# FAN-zero25-SHIM.net
KiCad netlist of a schematic drawn in EAGLE
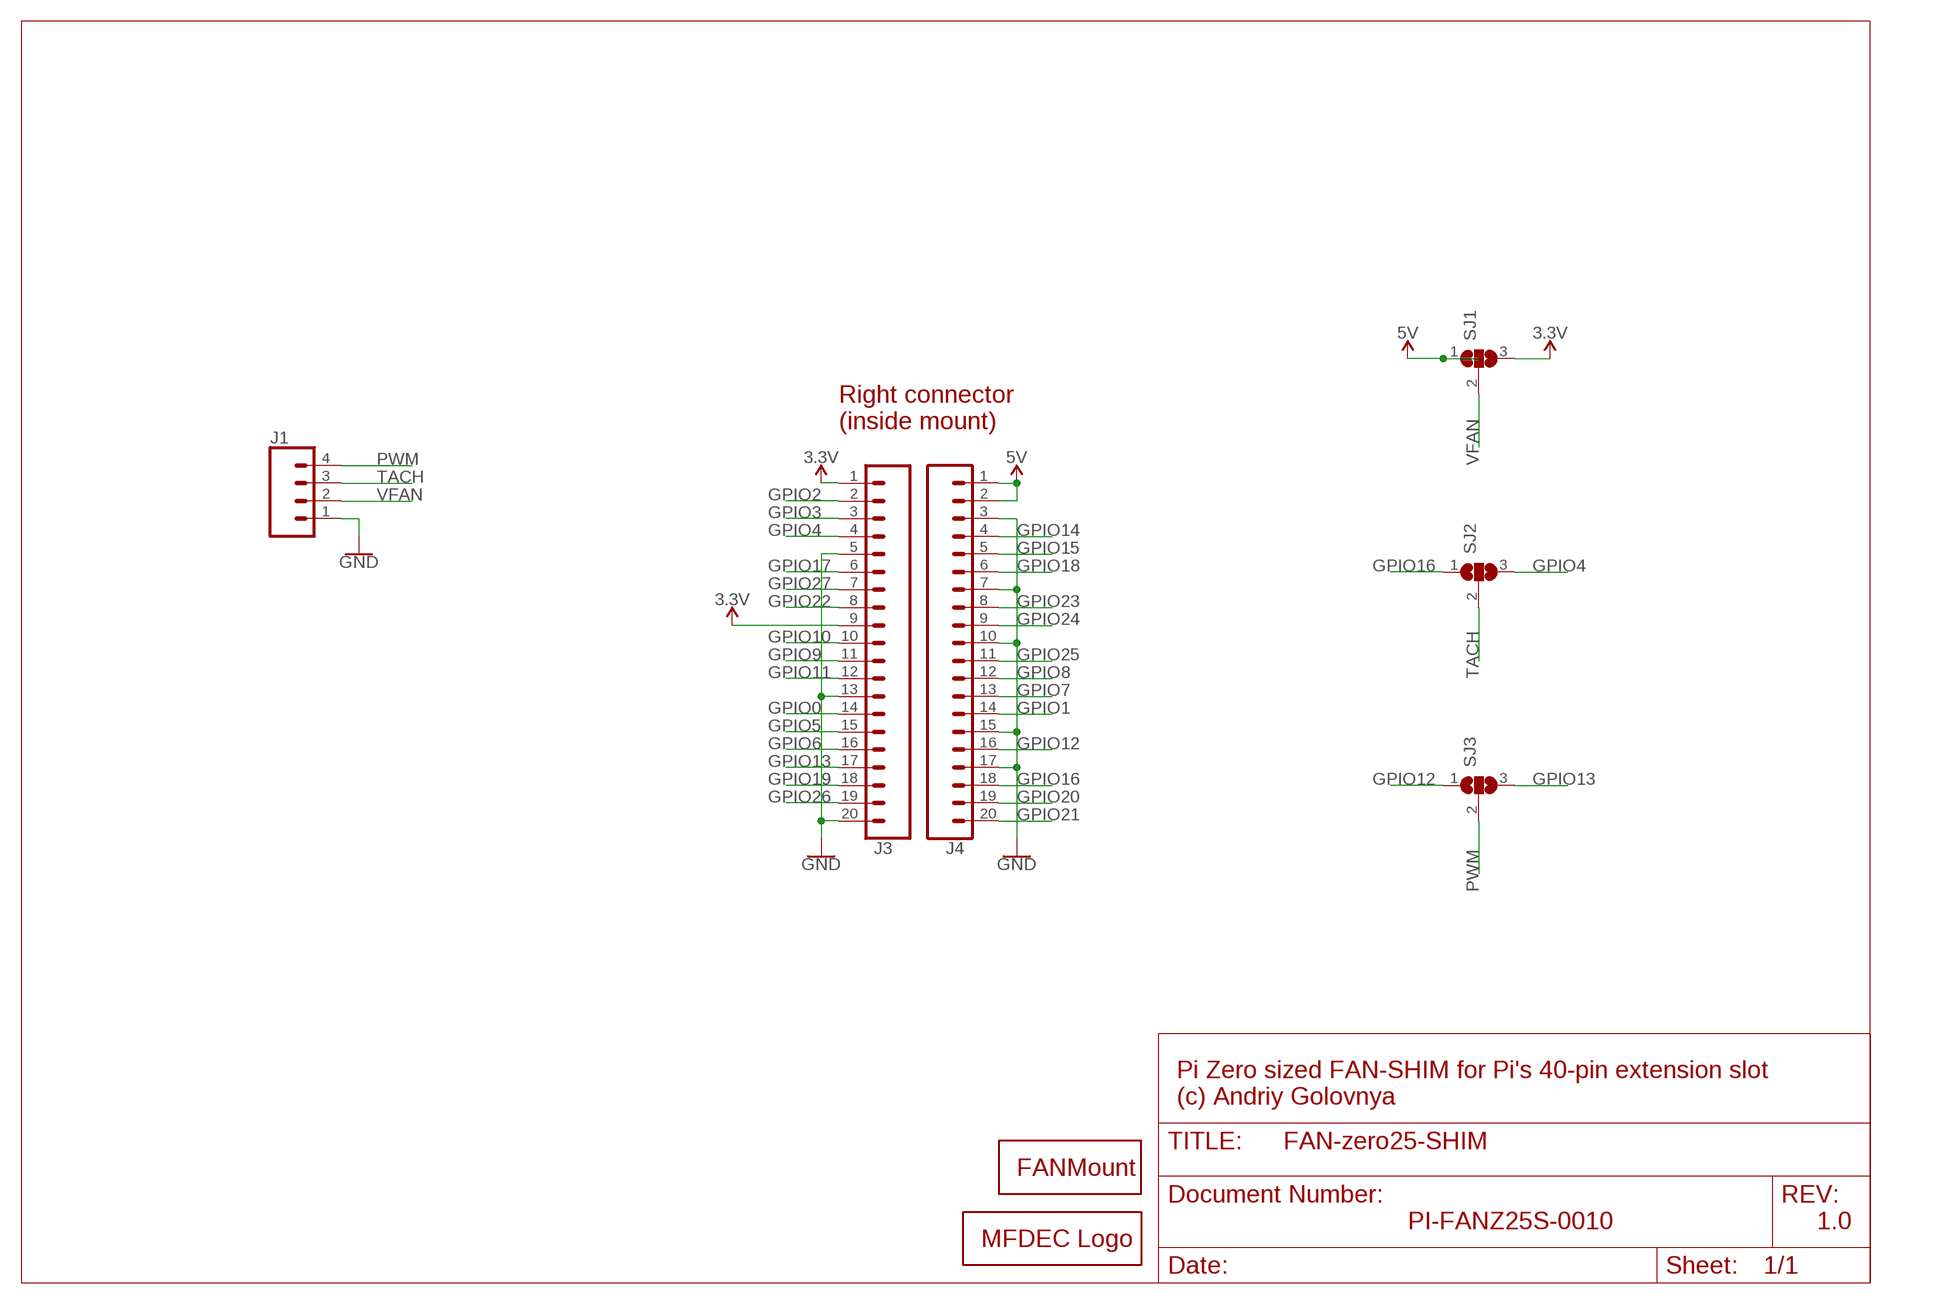
[diagram p0: schematic, sheet 1]

(export (version "E")
  (design (tool "Eeschema 10.0.6"))
  (components
    (comp (ref "FAN1")
      (value "FAN25HO")
      (footprint "eagle-import:FAN25HO")
      (libsource (lib "eagle-import") (part "FAN25HO"))
    )
    (comp (ref "J1")
      (value "CONN_04")
      (footprint "eagle-import:1X04")
      (libsource (lib "eagle-import") (part "CONN_04"))
    )
    (comp (ref "J3")
      (value "CONN_20LOCK")
      (footprint "eagle-import:1X20_LOCK")
      (libsource (lib "eagle-import") (part "CONN_20LOCK"))
    )
    (comp (ref "J4")
      (value "CONN_20LOCK")
      (footprint "eagle-import:1X20_LOCK")
      (libsource (lib "eagle-import") (part "CONN_20LOCK"))
    )
    (comp (ref "LOGO1")
      (value "MFDECLOGO_L_30MM")
      (footprint "eagle-import:MFDEC_L_30MM")
      (libsource (lib "eagle-import") (part "MFDECLOGO_L_30MM"))
    )
    (comp (ref "SJ1")
      (value "SJ2")
      (footprint "eagle-import:SJ_2")
      (libsource (lib "eagle-import") (part "SJ2"))
    )
    (comp (ref "SJ2")
      (value "SJ2")
      (footprint "eagle-import:SJ_2")
      (libsource (lib "eagle-import") (part "SJ2"))
    )
    (comp (ref "SJ3")
      (value "SJ2")
      (footprint "eagle-import:SJ_2")
      (libsource (lib "eagle-import") (part "SJ2"))
    )
  )
  (nets
    (net (code "1") (name "/GPIO0") (class "Default")
      (node (ref "J3") (pin "14") (pinfunction "14_14") (pintype "passive"))
    )
    (net (code "2") (name "/GPIO1") (class "Default")
      (node (ref "J4") (pin "14") (pinfunction "14_14") (pintype "passive"))
    )
    (net (code "3") (name "/GPIO2") (class "Default")
      (node (ref "J3") (pin "2") (pinfunction "2_2") (pintype "passive"))
    )
    (net (code "4") (name "/GPIO3") (class "Default")
      (node (ref "J3") (pin "3") (pinfunction "3_3") (pintype "passive"))
    )
    (net (code "5") (name "/GPIO4") (class "Default")
      (node (ref "J3") (pin "4") (pinfunction "4_4") (pintype "passive"))
      (node (ref "SJ2") (pin "3") (pinfunction "3_3") (pintype "passive"))
    )
    (net (code "6") (name "/GPIO5") (class "Default")
      (node (ref "J3") (pin "15") (pinfunction "15_15") (pintype "passive"))
    )
    (net (code "7") (name "/GPIO6") (class "Default")
      (node (ref "J3") (pin "16") (pinfunction "16_16") (pintype "passive"))
    )
    (net (code "8") (name "/GPIO7") (class "Default")
      (node (ref "J4") (pin "13") (pinfunction "13_13") (pintype "passive"))
    )
    (net (code "9") (name "/GPIO8") (class "Default")
      (node (ref "J4") (pin "12") (pinfunction "12_12") (pintype "passive"))
    )
    (net (code "10") (name "/GPIO9") (class "Default")
      (node (ref "J3") (pin "11") (pinfunction "11_11") (pintype "passive"))
    )
    (net (code "11") (name "/GPIO10") (class "Default")
      (node (ref "J3") (pin "10") (pinfunction "10_10") (pintype "passive"))
    )
    (net (code "12") (name "/GPIO11") (class "Default")
      (node (ref "J3") (pin "12") (pinfunction "12_12") (pintype "passive"))
    )
    (net (code "13") (name "/GPIO12") (class "Default")
      (node (ref "J4") (pin "16") (pinfunction "16_16") (pintype "passive"))
      (node (ref "SJ3") (pin "1") (pinfunction "1_1") (pintype "passive"))
    )
    (net (code "14") (name "/GPIO13") (class "Default")
      (node (ref "J3") (pin "17") (pinfunction "17_17") (pintype "passive"))
      (node (ref "SJ3") (pin "3") (pinfunction "3_3") (pintype "passive"))
    )
    (net (code "15") (name "/GPIO14") (class "Default")
      (node (ref "J4") (pin "4") (pinfunction "4_4") (pintype "passive"))
    )
    (net (code "16") (name "/GPIO15") (class "Default")
      (node (ref "J4") (pin "5") (pinfunction "5_5") (pintype "passive"))
    )
    (net (code "17") (name "/GPIO16") (class "Default")
      (node (ref "J4") (pin "18") (pinfunction "18_18") (pintype "passive"))
      (node (ref "SJ2") (pin "1") (pinfunction "1_1") (pintype "passive"))
    )
    (net (code "18") (name "/GPIO17") (class "Default")
      (node (ref "J3") (pin "6") (pinfunction "6_6") (pintype "passive"))
    )
    (net (code "19") (name "/GPIO18") (class "Default")
      (node (ref "J4") (pin "6") (pinfunction "6_6") (pintype "passive"))
    )
    (net (code "20") (name "/GPIO19") (class "Default")
      (node (ref "J3") (pin "18") (pinfunction "18_18") (pintype "passive"))
    )
    (net (code "21") (name "/GPIO20") (class "Default")
      (node (ref "J4") (pin "19") (pinfunction "19_19") (pintype "passive"))
    )
    (net (code "22") (name "/GPIO21") (class "Default")
      (node (ref "J4") (pin "20") (pinfunction "20_20") (pintype "passive"))
    )
    (net (code "23") (name "/GPIO22") (class "Default")
      (node (ref "J3") (pin "8") (pinfunction "8_8") (pintype "passive"))
    )
    (net (code "24") (name "/GPIO23") (class "Default")
      (node (ref "J4") (pin "8") (pinfunction "8_8") (pintype "passive"))
    )
    (net (code "25") (name "/GPIO24") (class "Default")
      (node (ref "J4") (pin "9") (pinfunction "9_9") (pintype "passive"))
    )
    (net (code "26") (name "/GPIO25") (class "Default")
      (node (ref "J4") (pin "11") (pinfunction "11_11") (pintype "passive"))
    )
    (net (code "27") (name "/GPIO26") (class "Default")
      (node (ref "J3") (pin "19") (pinfunction "19_19") (pintype "passive"))
    )
    (net (code "28") (name "/GPIO27") (class "Default")
      (node (ref "J3") (pin "7") (pinfunction "7_7") (pintype "passive"))
    )
    (net (code "29") (name "/PWM") (class "Default")
      (node (ref "J1") (pin "4") (pinfunction "4_4") (pintype "passive"))
      (node (ref "SJ3") (pin "2") (pinfunction "2_2") (pintype "passive"))
    )
    (net (code "30") (name "/TACH") (class "Default")
      (node (ref "J1") (pin "3") (pinfunction "3_3") (pintype "passive"))
      (node (ref "SJ2") (pin "2") (pinfunction "2_2") (pintype "passive"))
    )
    (net (code "31") (name "/VFAN") (class "Default")
      (node (ref "J1") (pin "2") (pinfunction "2_2") (pintype "passive"))
      (node (ref "SJ1") (pin "2") (pinfunction "2_2") (pintype "passive"))
    )
    (net (code "32") (name "3.3V") (class "Default")
      (node (ref "J3") (pin "1") (pinfunction "1_1") (pintype "passive"))
      (node (ref "J3") (pin "9") (pinfunction "9_9") (pintype "passive"))
      (node (ref "SJ1") (pin "3") (pinfunction "3_3") (pintype "passive"))
    )
    (net (code "33") (name "5V") (class "Default")
      (node (ref "J4") (pin "1") (pinfunction "1_1") (pintype "passive"))
      (node (ref "J4") (pin "2") (pinfunction "2_2") (pintype "passive"))
      (node (ref "SJ1") (pin "1") (pinfunction "1_1") (pintype "passive"))
    )
    (net (code "34") (name "GND") (class "Default")
      (node (ref "J1") (pin "1") (pinfunction "1_1") (pintype "passive"))
      (node (ref "J3") (pin "13") (pinfunction "13_13") (pintype "passive"))
      (node (ref "J3") (pin "20") (pinfunction "20_20") (pintype "passive"))
      (node (ref "J3") (pin "5") (pinfunction "5_5") (pintype "passive"))
      (node (ref "J4") (pin "10") (pinfunction "10_10") (pintype "passive"))
      (node (ref "J4") (pin "15") (pinfunction "15_15") (pintype "passive"))
      (node (ref "J4") (pin "17") (pinfunction "17_17") (pintype "passive"))
      (node (ref "J4") (pin "3") (pinfunction "3_3") (pintype "passive"))
      (node (ref "J4") (pin "7") (pinfunction "7_7") (pintype "passive"))
    )
  )
)
